# ESP12-1wire.net
KiCad netlist of a schematic drawn in EAGLE
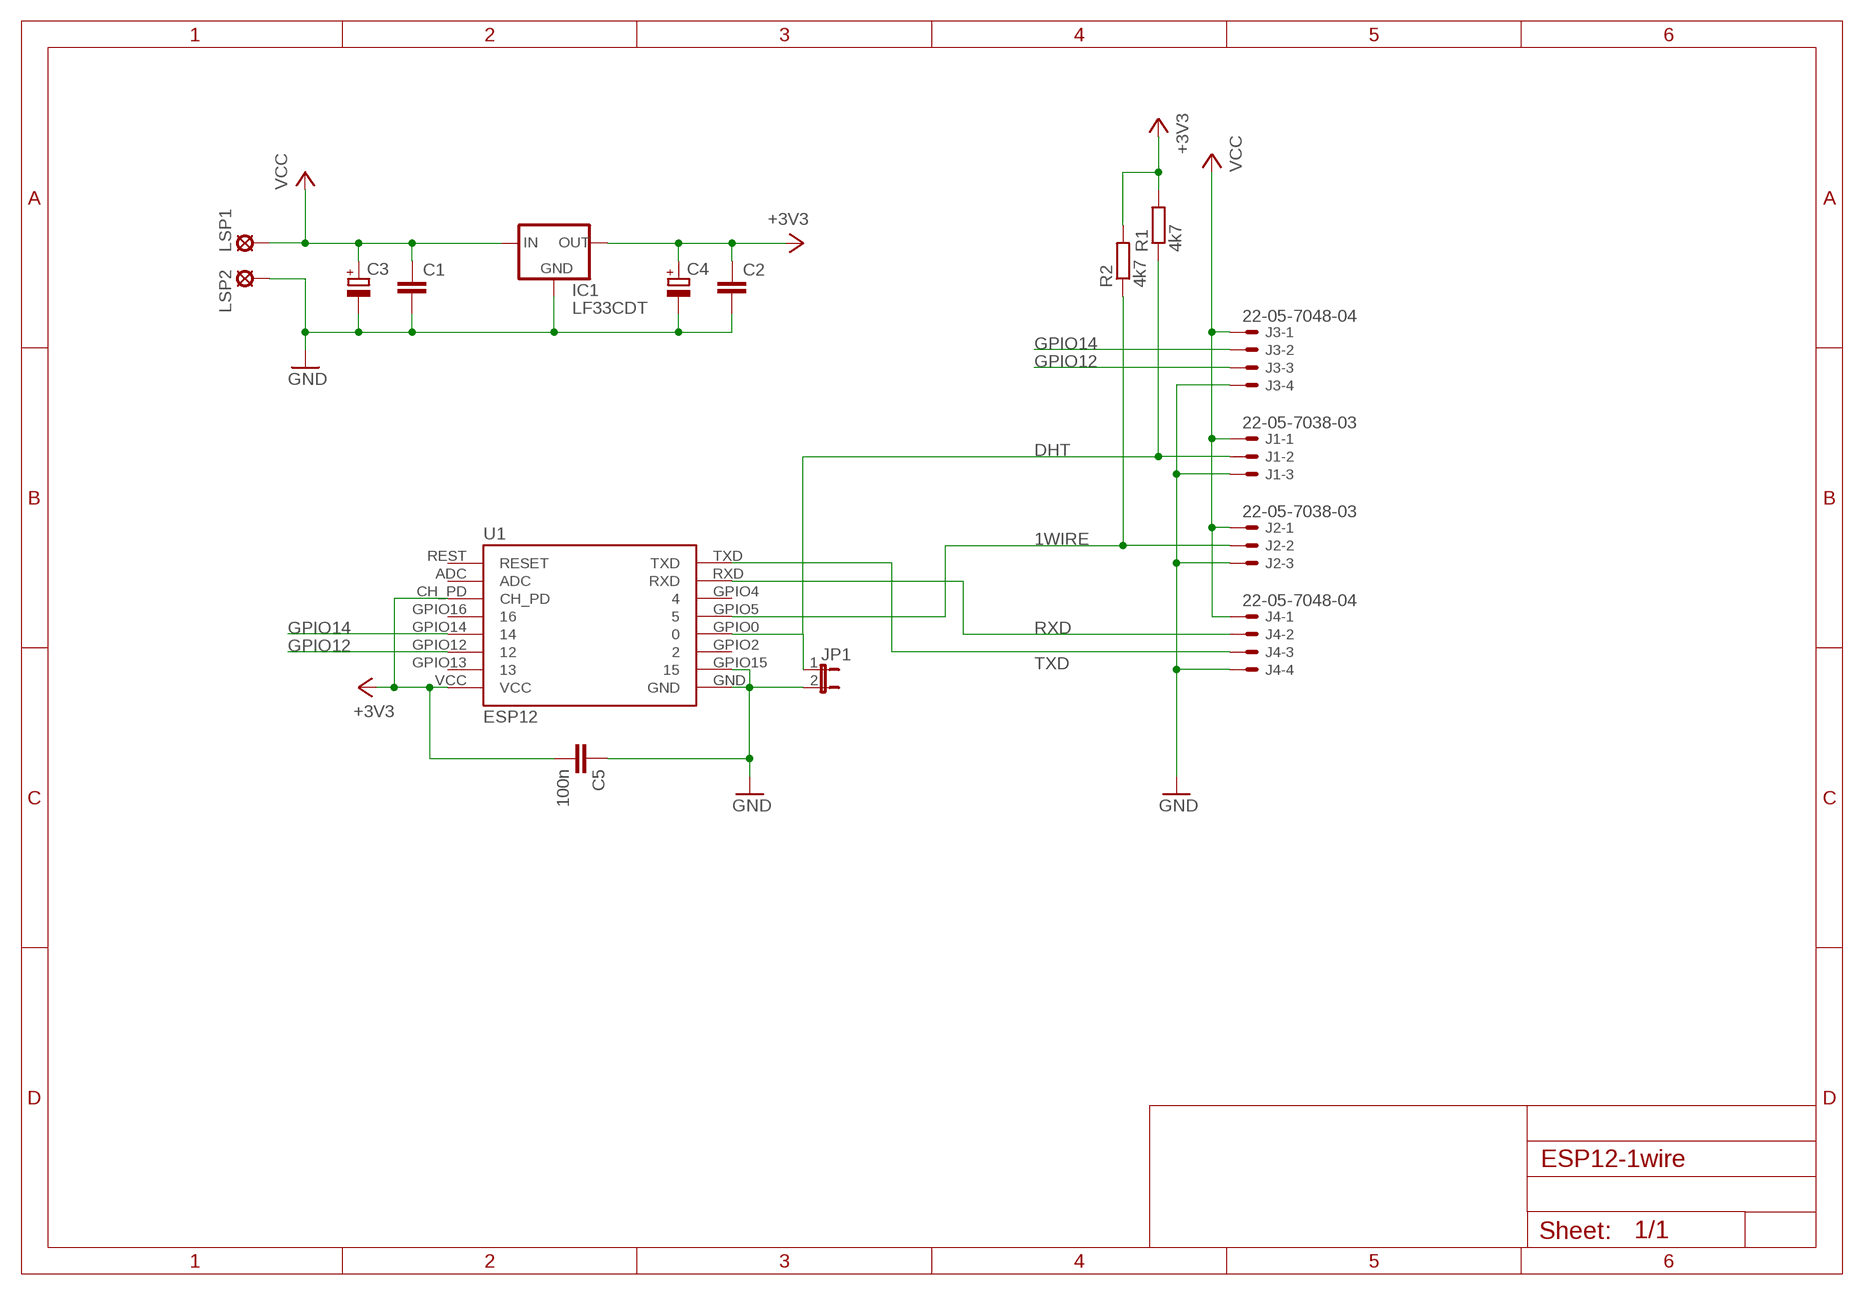
[diagram p0: schematic, sheet 1]

(export (version "E")
  (design (tool "Eeschema 10.0.6"))
  (components
    (comp (ref "C1")
      (value "C-EUC0805")
      (footprint "eagle-import:C0805")
      (libsource (lib "eagle-import") (part "C-EUC0805"))
    )
    (comp (ref "C2")
      (value "C-EUC0805")
      (footprint "eagle-import:C0805")
      (libsource (lib "eagle-import") (part "C-EUC0805"))
    )
    (comp (ref "C3")
      (value "CPOL-EUSMCA")
      (footprint "eagle-import:SMC_A")
      (libsource (lib "eagle-import") (part "CPOL-EUSMCA"))
    )
    (comp (ref "C4")
      (value "CPOL-EUSMCA")
      (footprint "eagle-import:SMC_A")
      (libsource (lib "eagle-import") (part "CPOL-EUSMCA"))
    )
    (comp (ref "C5")
      (value "100n")
      (footprint "eagle-import:C0805")
      (libsource (lib "eagle-import") (part "C-EUC0805"))
    )
    (comp (ref "IC1")
      (value "LF33CDT")
      (footprint "eagle-import:DPACK")
      (libsource (lib "eagle-import") (part "LP2950?CDT-3.3"))
    )
    (comp (ref "J1")
      (value "22-05-7038-03")
      (footprint "eagle-import:7395-03")
      (libsource (lib "eagle-import") (part "22-?-0305-7038"))
    )
    (comp (ref "J2")
      (value "22-05-7038-03")
      (footprint "eagle-import:7395-03")
      (libsource (lib "eagle-import") (part "22-?-0305-7038"))
    )
    (comp (ref "J3")
      (value "22-05-7048-04")
      (footprint "eagle-import:7395-04")
      (libsource (lib "eagle-import") (part "22-?-0405-7048"))
    )
    (comp (ref "J4")
      (value "22-05-7048-04")
      (footprint "eagle-import:7395-04")
      (libsource (lib "eagle-import") (part "22-?-0405-7048"))
    )
    (comp (ref "JP1")
      (value "JP1E")
      (footprint "eagle-import:JP1")
      (libsource (lib "eagle-import") (part "JP1E"))
    )
    (comp (ref "LSP1")
      (value "LSP10")
      (footprint "eagle-import:LSP10")
      (libsource (lib "eagle-import") (part "LSP10"))
    )
    (comp (ref "LSP2")
      (value "LSP10")
      (footprint "eagle-import:LSP10")
      (libsource (lib "eagle-import") (part "LSP10"))
    )
    (comp (ref "R1")
      (value "4k7")
      (footprint "eagle-import:R0805")
      (libsource (lib "eagle-import") (part "R-EU_R0805"))
    )
    (comp (ref "R2")
      (value "4k7")
      (footprint "eagle-import:R0805")
      (libsource (lib "eagle-import") (part "R-EU_R0805"))
    )
    (comp (ref "U1")
      (value "ESP12")
      (footprint "eagle-import:ESP12")
      (libsource (lib "eagle-import") (part "ESP12"))
    )
  )
  (nets
    (net (code "1") (name "+3V3") (class "Default")
      (node (ref "C2") (pin "1") (pinfunction "1_1") (pintype "passive"))
      (node (ref "C4") (pin "+") (pinfunction "+_+") (pintype "passive"))
      (node (ref "C5") (pin "2") (pinfunction "2_2") (pintype "passive"))
      (node (ref "IC1") (pin "3") (pinfunction "OUT_3") (pintype "passive"))
      (node (ref "R1") (pin "2") (pinfunction "2_2") (pintype "passive"))
      (node (ref "R2") (pin "2") (pinfunction "2_2") (pintype "passive"))
      (node (ref "U1") (pin "CH_PD") (pinfunction "CH_PD_CH_PD") (pintype "input"))
      (node (ref "U1") (pin "VCC") (pinfunction "VCC_VCC") (pintype "power_in"))
    )
    (net (code "2") (name "/1WIRE") (class "Default")
      (node (ref "J2") (pin "2") (pinfunction "S_2") (pintype "passive"))
      (node (ref "R2") (pin "1") (pinfunction "1_1") (pintype "passive"))
      (node (ref "U1") (pin "GPIO5") (pinfunction "5_GPIO5") (pintype "bidirectional"))
    )
    (net (code "3") (name "/DHT") (class "Default")
      (node (ref "J1") (pin "2") (pinfunction "S_2") (pintype "passive"))
      (node (ref "JP1") (pin "1") (pinfunction "1_1") (pintype "passive"))
      (node (ref "R1") (pin "1") (pinfunction "1_1") (pintype "passive"))
      (node (ref "U1") (pin "GPIO0") (pinfunction "0_GPIO0") (pintype "bidirectional"))
    )
    (net (code "4") (name "/GPIO12") (class "Default")
      (node (ref "J3") (pin "3") (pinfunction "S_3") (pintype "passive"))
      (node (ref "U1") (pin "GPIO12") (pinfunction "12_GPIO12") (pintype "bidirectional"))
    )
    (net (code "5") (name "/GPIO14") (class "Default")
      (node (ref "J3") (pin "2") (pinfunction "S_2") (pintype "passive"))
      (node (ref "U1") (pin "GPIO14") (pinfunction "14_GPIO14") (pintype "bidirectional"))
    )
    (net (code "6") (name "/RXD") (class "Default")
      (node (ref "J4") (pin "2") (pinfunction "S_2") (pintype "passive"))
      (node (ref "U1") (pin "RXD") (pinfunction "RXD_RXD") (pintype "output"))
    )
    (net (code "7") (name "/TXD") (class "Default")
      (node (ref "J4") (pin "3") (pinfunction "S_3") (pintype "passive"))
      (node (ref "U1") (pin "TXD") (pinfunction "TXD_TXD") (pintype "input"))
    )
    (net (code "8") (name "GND") (class "Default")
      (node (ref "C1") (pin "2") (pinfunction "2_2") (pintype "passive"))
      (node (ref "C2") (pin "2") (pinfunction "2_2") (pintype "passive"))
      (node (ref "C3") (pin "-") (pinfunction "-_-") (pintype "passive"))
      (node (ref "C4") (pin "-") (pinfunction "-_-") (pintype "passive"))
      (node (ref "C5") (pin "1") (pinfunction "1_1") (pintype "passive"))
      (node (ref "IC1") (pin "4") (pinfunction "GND_4") (pintype "input"))
      (node (ref "J1") (pin "3") (pinfunction "S_3") (pintype "passive"))
      (node (ref "J2") (pin "3") (pinfunction "S_3") (pintype "passive"))
      (node (ref "J3") (pin "4") (pinfunction "S_4") (pintype "passive"))
      (node (ref "J4") (pin "4") (pinfunction "S_4") (pintype "passive"))
      (node (ref "JP1") (pin "2") (pinfunction "2_2") (pintype "passive"))
      (node (ref "LSP2") (pin "MP") (pinfunction "MP_MP") (pintype "passive"))
      (node (ref "U1") (pin "GND") (pinfunction "GND_GND") (pintype "power_in"))
      (node (ref "U1") (pin "GPIO15") (pinfunction "15_GPIO15") (pintype "bidirectional"))
    )
    (net (code "9") (name "VCC") (class "Default")
      (node (ref "C1") (pin "1") (pinfunction "1_1") (pintype "passive"))
      (node (ref "C3") (pin "+") (pinfunction "+_+") (pintype "passive"))
      (node (ref "IC1") (pin "1") (pinfunction "IN_1") (pintype "input"))
      (node (ref "J1") (pin "1") (pinfunction "S_1") (pintype "passive"))
      (node (ref "J2") (pin "1") (pinfunction "S_1") (pintype "passive"))
      (node (ref "J3") (pin "1") (pinfunction "S_1") (pintype "passive"))
      (node (ref "J4") (pin "1") (pinfunction "S_1") (pintype "passive"))
      (node (ref "LSP1") (pin "MP") (pinfunction "MP_MP") (pintype "passive"))
    )
    (net (code "10") (name "unconnected-(U1-2-PadGPIO2)") (class "Default")
      (node (ref "U1") (pin "GPIO2") (pinfunction "2_GPIO2") (pintype "bidirectional"))
    )
    (net (code "11") (name "unconnected-(U1-4-PadGPIO4)") (class "Default")
      (node (ref "U1") (pin "GPIO4") (pinfunction "4_GPIO4") (pintype "bidirectional"))
    )
    (net (code "12") (name "unconnected-(U1-13-PadGPIO13)") (class "Default")
      (node (ref "U1") (pin "GPIO13") (pinfunction "13_GPIO13") (pintype "bidirectional"))
    )
    (net (code "13") (name "unconnected-(U1-16-PadGPIO16)") (class "Default")
      (node (ref "U1") (pin "GPIO16") (pinfunction "16_GPIO16") (pintype "bidirectional"))
    )
    (net (code "14") (name "unconnected-(U1-PadADC)") (class "Default")
      (node (ref "U1") (pin "ADC") (pinfunction "ADC_ADC") (pintype "input"))
    )
    (net (code "15") (name "unconnected-(U1-RESET-PadREST)") (class "Default")
      (node (ref "U1") (pin "REST") (pinfunction "RESET_REST") (pintype "input"))
    )
  )
)
